# qsd_blank.net
KiCad netlist of a schematic drawn in Altium Designer
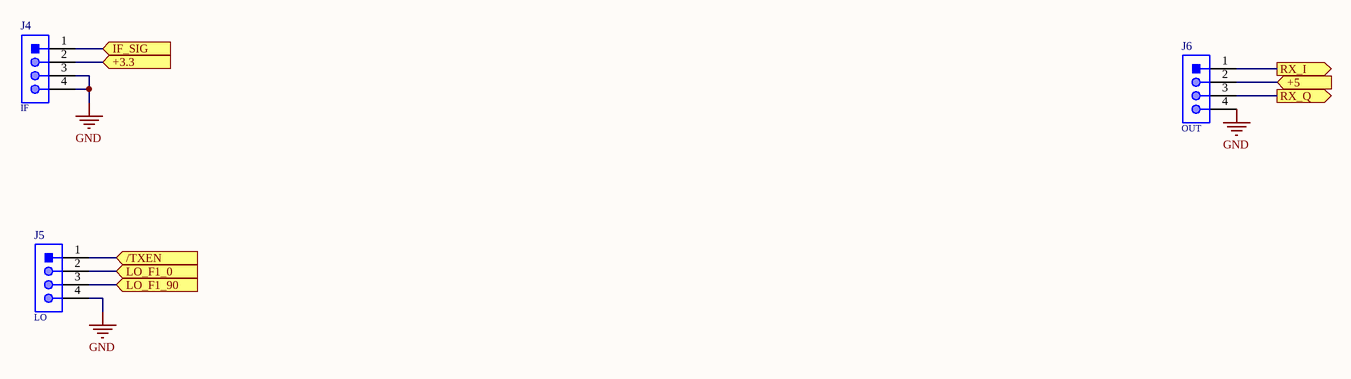
[diagram p0: qsd_blank.SchDoc]

(export (version "E")
  (design (tool "Eeschema 10.0.6"))
  (components
    (comp (ref "J4")
      (value "IF")
      (footprint "61300411121")
      (description "THT Vertical Pin Header WR-PHD, Pitch 2.54 mm, Single Row, 4 pins")
      (fields
        (field (name "MANUFACTURER") "Wurth Elektronik")
        (field (name "PART NUMBER") "61300411121")
        (field (name "PUBLISHER") "WurthElektronik")
      )
      (libsource (lib "Altium Content Vault") (part "WE-CN-1P-M-R4"))
    )
    (comp (ref "J5")
      (value "LO")
      (footprint "61300411121")
      (description "THT Vertical Pin Header WR-PHD, Pitch 2.54 mm, Single Row, 4 pins")
      (fields
        (field (name "MANUFACTURER") "Wurth Elektronik")
        (field (name "PART NUMBER") "61300411121")
        (field (name "PUBLISHER") "WurthElektronik")
      )
      (libsource (lib "Altium Content Vault") (part "WE-CN-1P-M-R4"))
    )
    (comp (ref "J6")
      (value "OUT")
      (footprint "61300411121")
      (description "THT Vertical Pin Header WR-PHD, Pitch 2.54 mm, Single Row, 4 pins")
      (fields
        (field (name "MANUFACTURER") "Wurth Elektronik")
        (field (name "PART NUMBER") "61300411121")
        (field (name "PUBLISHER") "WurthElektronik")
      )
      (libsource (lib "Altium Content Vault") (part "WE-CN-1P-M-R4"))
    )
  )
  (nets
    (net (code "1") (name "/+3.3") (class "Default")
      (node (ref "J4") (pin "2") (pinfunction "2_2") (pintype "passive"))
    )
    (net (code "2") (name "/+5") (class "Default")
      (node (ref "J6") (pin "2") (pinfunction "2_2") (pintype "passive"))
    )
    (net (code "3") (name "/IF_SIG") (class "Default")
      (node (ref "J4") (pin "1") (pinfunction "1_1") (pintype "passive"))
    )
    (net (code "4") (name "/LO_F1_0") (class "Default")
      (node (ref "J5") (pin "2") (pinfunction "2_2") (pintype "passive"))
    )
    (net (code "5") (name "/LO_F1_90") (class "Default")
      (node (ref "J5") (pin "3") (pinfunction "3_3") (pintype "passive"))
    )
    (net (code "6") (name "/RX_I") (class "Default")
      (node (ref "J6") (pin "1") (pinfunction "1_1") (pintype "passive"))
    )
    (net (code "7") (name "/RX_Q") (class "Default")
      (node (ref "J6") (pin "3") (pinfunction "3_3") (pintype "passive"))
    )
    (net (code "8") (name "/{slash}TXEN") (class "Default")
      (node (ref "J5") (pin "1") (pinfunction "1_1") (pintype "passive"))
    )
    (net (code "9") (name "GND") (class "Default")
      (node (ref "J4") (pin "3") (pinfunction "3_3") (pintype "passive"))
      (node (ref "J4") (pin "4") (pinfunction "4_4") (pintype "passive"))
      (node (ref "J5") (pin "4") (pinfunction "4_4") (pintype "passive"))
      (node (ref "J6") (pin "4") (pinfunction "4_4") (pintype "passive"))
    )
  )
)
